# 7_-RGMII_SDIO_SPI_GPIOs_etc.net
KiCad netlist of a schematic drawn in Altium Designer
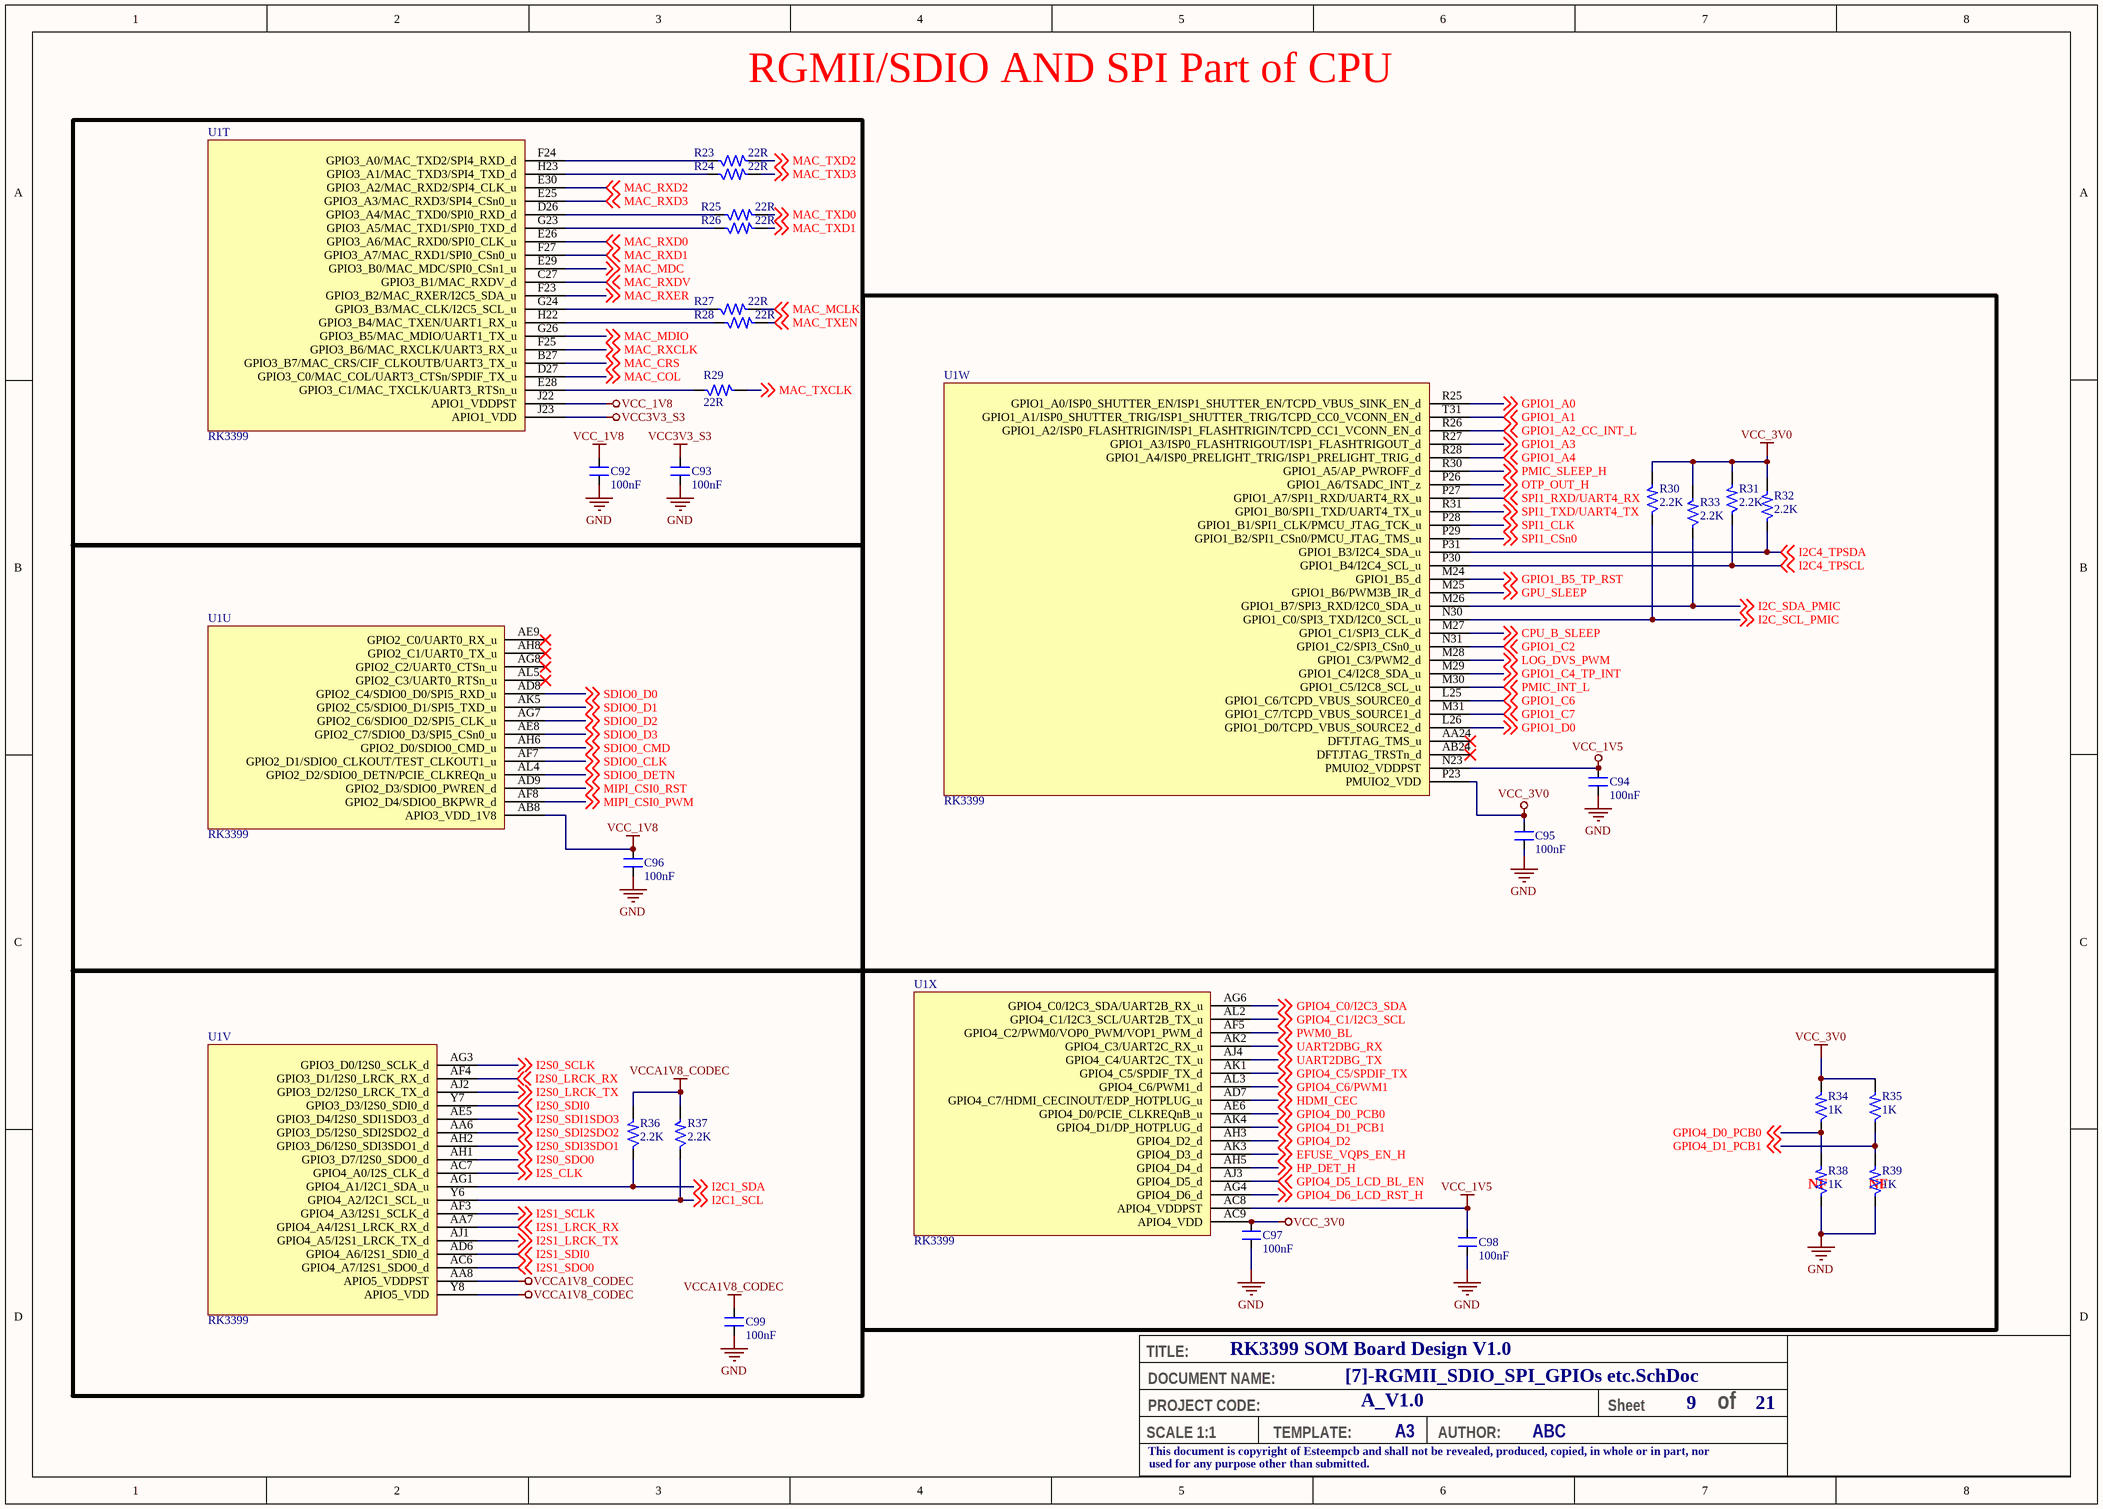
[diagram p0: [7]-RGMII_SDIO_SPI_GPIOs etc.SchDoc]

(export (version "E")
  (design (tool "Eeschema 10.0.6"))
  (components
    (comp (ref "C92")
      (value "100nF")
      (footprint "CAP_0201")
      (description "0.1µF ±10% 25V Ceramic Capacitor X5R 0201 (0603 Metric)")
      (fields
        (field (name "MANUFACTURER") "TDK Corporation")
        (field (name "MANUFACTURER PART NUMBER") "C0603X5R1E104K030BB")
      )
      (libsource (lib "RK3399 _Module_Intlib") (part "CAP_100nF-25V-10%-0201"))
    )
    (comp (ref "C93")
      (value "100nF")
      (footprint "CAP_0201")
      (description "0.1µF ±10% 25V Ceramic Capacitor X5R 0201 (0603 Metric)")
      (fields
        (field (name "MANUFACTURER") "TDK Corporation")
        (field (name "MANUFACTURER PART NUMBER") "C0603X5R1E104K030BB")
      )
      (libsource (lib "RK3399 _Module_Intlib") (part "CAP_100nF-25V-10%-0201"))
    )
    (comp (ref "C94")
      (value "100nF")
      (footprint "CAP_0201")
      (description "0.1µF ±10% 25V Ceramic Capacitor X5R 0201 (0603 Metric)")
      (fields
        (field (name "MANUFACTURER") "TDK Corporation")
        (field (name "MANUFACTURER PART NUMBER") "C0603X5R1E104K030BB")
      )
      (libsource (lib "RK3399 _Module_Intlib") (part "CAP_100nF-25V-10%-0201"))
    )
    (comp (ref "C95")
      (value "100nF")
      (footprint "CAP_0201")
      (description "0.1µF ±10% 25V Ceramic Capacitor X5R 0201 (0603 Metric)")
      (fields
        (field (name "MANUFACTURER") "TDK Corporation")
        (field (name "MANUFACTURER PART NUMBER") "C0603X5R1E104K030BB")
      )
      (libsource (lib "RK3399 _Module_Intlib") (part "CAP_100nF-25V-10%-0201"))
    )
    (comp (ref "C96")
      (value "100nF")
      (footprint "CAP_0201")
      (description "0.1µF ±10% 25V Ceramic Capacitor X5R 0201 (0603 Metric)")
      (fields
        (field (name "MANUFACTURER") "TDK Corporation")
        (field (name "MANUFACTURER PART NUMBER") "C0603X5R1E104K030BB")
      )
      (libsource (lib "RK3399 _Module_Intlib") (part "CAP_100nF-25V-10%-0201"))
    )
    (comp (ref "C97")
      (value "100nF")
      (footprint "CAP_0201")
      (description "0.1µF ±10% 25V Ceramic Capacitor X5R 0201 (0603 Metric)")
      (fields
        (field (name "MANUFACTURER") "TDK Corporation")
        (field (name "MANUFACTURER PART NUMBER") "C0603X5R1E104K030BB")
      )
      (libsource (lib "RK3399 _Module_Intlib") (part "CAP_100nF-25V-10%-0201"))
    )
    (comp (ref "C98")
      (value "100nF")
      (footprint "CAP_0201")
      (description "0.1µF ±10% 25V Ceramic Capacitor X5R 0201 (0603 Metric)")
      (fields
        (field (name "MANUFACTURER") "TDK Corporation")
        (field (name "MANUFACTURER PART NUMBER") "C0603X5R1E104K030BB")
      )
      (libsource (lib "RK3399 _Module_Intlib") (part "CAP_100nF-25V-10%-0201"))
    )
    (comp (ref "C99")
      (value "100nF")
      (footprint "CAP_0201")
      (description "0.1µF ±10% 25V Ceramic Capacitor X5R 0201 (0603 Metric)")
      (fields
        (field (name "MANUFACTURER") "TDK Corporation")
        (field (name "MANUFACTURER PART NUMBER") "C0603X5R1E104K030BB")
      )
      (libsource (lib "RK3399 _Module_Intlib") (part "CAP_100nF-25V-10%-0201"))
    )
    (comp (ref "R23")
      (value "22R")
      (footprint "RES_0201")
      (description "22 Ohms ±1% 0.05W, 1/20W Chip Resistor 0201 (0603 Metric) Moisture Resistant Thick Film")
      (fields
        (field (name "MANUFACTURER") "Yageo")
        (field (name "MANUFACTURER PART NUMBER") "RC0201FR-0722RL")
      )
      (libsource (lib "EsteemPCB_SOM_Course_intlib") (part "RES_22R-0.05W-1%-0201"))
    )
    (comp (ref "R24")
      (value "22R")
      (footprint "RES_0201")
      (description "22 Ohms ±1% 0.05W, 1/20W Chip Resistor 0201 (0603 Metric) Moisture Resistant Thick Film")
      (fields
        (field (name "MANUFACTURER") "Yageo")
        (field (name "MANUFACTURER PART NUMBER") "RC0201FR-0722RL")
      )
      (libsource (lib "EsteemPCB_SOM_Course_intlib") (part "RES_22R-0.05W-1%-0201"))
    )
    (comp (ref "R25")
      (value "22R")
      (footprint "RES_0201")
      (description "22 Ohms ±1% 0.05W, 1/20W Chip Resistor 0201 (0603 Metric) Moisture Resistant Thick Film")
      (fields
        (field (name "MANUFACTURER") "Yageo")
        (field (name "MANUFACTURER PART NUMBER") "RC0201FR-0722RL")
      )
      (libsource (lib "EsteemPCB_SOM_Course_intlib") (part "RES_22R-0.05W-1%-0201"))
    )
    (comp (ref "R26")
      (value "22R")
      (footprint "RES_0201")
      (description "22 Ohms ±1% 0.05W, 1/20W Chip Resistor 0201 (0603 Metric) Moisture Resistant Thick Film")
      (fields
        (field (name "MANUFACTURER") "Yageo")
        (field (name "MANUFACTURER PART NUMBER") "RC0201FR-0722RL")
      )
      (libsource (lib "EsteemPCB_SOM_Course_intlib") (part "RES_22R-0.05W-1%-0201"))
    )
    (comp (ref "R27")
      (value "22R")
      (footprint "RES_0201")
      (description "22 Ohms ±1% 0.05W, 1/20W Chip Resistor 0201 (0603 Metric) Moisture Resistant Thick Film")
      (fields
        (field (name "MANUFACTURER") "Yageo")
        (field (name "MANUFACTURER PART NUMBER") "RC0201FR-0722RL")
      )
      (libsource (lib "EsteemPCB_SOM_Course_intlib") (part "RES_22R-0.05W-1%-0201"))
    )
    (comp (ref "R28")
      (value "22R")
      (footprint "RES_0201")
      (description "22 Ohms ±1% 0.05W, 1/20W Chip Resistor 0201 (0603 Metric) Moisture Resistant Thick Film")
      (fields
        (field (name "MANUFACTURER") "Yageo")
        (field (name "MANUFACTURER PART NUMBER") "RC0201FR-0722RL")
      )
      (libsource (lib "EsteemPCB_SOM_Course_intlib") (part "RES_22R-0.05W-1%-0201"))
    )
    (comp (ref "R29")
      (value "22R")
      (footprint "RES_0201")
      (description "22 Ohms ±1% 0.05W, 1/20W Chip Resistor 0201 (0603 Metric) Moisture Resistant Thick Film")
      (fields
        (field (name "MANUFACTURER") "Yageo")
        (field (name "MANUFACTURER PART NUMBER") "RC0201FR-0722RL")
      )
      (libsource (lib "EsteemPCB_SOM_Course_intlib") (part "RES_22R-0.05W-1%-0201"))
    )
    (comp (ref "R30")
      (value "2.2K")
      (footprint "RES_0201")
      (description "2.2 kOhms ±1% 0.05W, 1/20W Chip Resistor 0201 (0603 Metric) Thick Film")
      (fields
        (field (name "MANUFACTURER") "Stackpole Electronics Inc")
        (field (name "MANUFACTURER PART NUMBER") "RMCF0201FT2K20")
      )
      (libsource (lib "RK3399 _Module_Intlib") (part "RES_2.2K-0.05W-1%-0201"))
    )
    (comp (ref "R31")
      (value "2.2K")
      (footprint "RES_0201")
      (description "2.2 kOhms ±1% 0.05W, 1/20W Chip Resistor 0201 (0603 Metric) Thick Film")
      (fields
        (field (name "MANUFACTURER") "Stackpole Electronics Inc")
        (field (name "MANUFACTURER PART NUMBER") "RMCF0201FT2K20")
      )
      (libsource (lib "RK3399 _Module_Intlib") (part "RES_2.2K-0.05W-1%-0201"))
    )
    (comp (ref "R32")
      (value "2.2K")
      (footprint "RES_0201")
      (description "2.2 kOhms ±1% 0.05W, 1/20W Chip Resistor 0201 (0603 Metric) Thick Film")
      (fields
        (field (name "MANUFACTURER") "Stackpole Electronics Inc")
        (field (name "MANUFACTURER PART NUMBER") "RMCF0201FT2K20")
      )
      (libsource (lib "RK3399 _Module_Intlib") (part "RES_2.2K-0.05W-1%-0201"))
    )
    (comp (ref "R33")
      (value "2.2K")
      (footprint "RES_0201")
      (description "2.2 kOhms ±1% 0.05W, 1/20W Chip Resistor 0201 (0603 Metric) Thick Film")
      (fields
        (field (name "MANUFACTURER") "Stackpole Electronics Inc")
        (field (name "MANUFACTURER PART NUMBER") "RMCF0201FT2K20")
      )
      (libsource (lib "RK3399 _Module_Intlib") (part "RES_2.2K-0.05W-1%-0201"))
    )
    (comp (ref "R34")
      (value "1K")
      (footprint "RES_0201")
      (description "1 kOhms ±1% 0.05W, 1/20W Chip Resistor 0201 (0603 Metric) Thick Film")
      (fields
        (field (name "MANUFACTURER") "Yageo")
        (field (name "MANUFACTURER PART NUMBER") "RC0201FR-071KL")
      )
      (libsource (lib "RK3399 _Module_Intlib") (part "RES_1K-0.05W-1%-0201"))
    )
    (comp (ref "R35")
      (value "1K")
      (footprint "RES_0201")
      (description "1 kOhms ±1% 0.05W, 1/20W Chip Resistor 0201 (0603 Metric) Thick Film")
      (fields
        (field (name "MANUFACTURER") "Yageo")
        (field (name "MANUFACTURER PART NUMBER") "RC0201FR-071KL")
      )
      (libsource (lib "RK3399 _Module_Intlib") (part "RES_1K-0.05W-1%-0201"))
    )
    (comp (ref "R36")
      (value "2.2K")
      (footprint "RES_0201")
      (description "2.2 kOhms ±1% 0.05W, 1/20W Chip Resistor 0201 (0603 Metric) Thick Film")
      (fields
        (field (name "MANUFACTURER") "Stackpole Electronics Inc")
        (field (name "MANUFACTURER PART NUMBER") "RMCF0201FT2K20")
      )
      (libsource (lib "RK3399 _Module_Intlib") (part "RES_2.2K-0.05W-1%-0201"))
    )
    (comp (ref "R37")
      (value "2.2K")
      (footprint "RES_0201")
      (description "2.2 kOhms ±1% 0.05W, 1/20W Chip Resistor 0201 (0603 Metric) Thick Film")
      (fields
        (field (name "MANUFACTURER") "Stackpole Electronics Inc")
        (field (name "MANUFACTURER PART NUMBER") "RMCF0201FT2K20")
      )
      (libsource (lib "RK3399 _Module_Intlib") (part "RES_2.2K-0.05W-1%-0201"))
    )
    (comp (ref "R38")
      (value "1K")
      (footprint "RES_0201")
      (description "1 kOhms ±1% 0.05W, 1/20W Chip Resistor 0201 (0603 Metric) Thick Film")
      (fields
        (field (name "MANUFACTURER") "Yageo")
        (field (name "MANUFACTURER PART NUMBER") "RC0201FR-071KL")
      )
      (libsource (lib "RK3399 _Module_Intlib") (part "RES_1K-0.05W-1%-0201"))
    )
    (comp (ref "R39")
      (value "1K")
      (footprint "RES_0201")
      (description "1 kOhms ±1% 0.05W, 1/20W Chip Resistor 0201 (0603 Metric) Thick Film")
      (fields
        (field (name "MANUFACTURER") "Yageo")
        (field (name "MANUFACTURER PART NUMBER") "RC0201FR-071KL")
      )
      (libsource (lib "RK3399 _Module_Intlib") (part "RES_1K-0.05W-1%-0201"))
    )
    (comp (ref "U1")
      (value "RK3399")
      (footprint "FBGA828_23_826X826")
      (description "RK3399 is a low power, high performance processor for computing, personal mobile.")
      (fields (field (name "MANUFACTURER") "Rockchip"))
      (libsource (lib "RK3399 _Module_Schlib") (part "IC_RK3399-FCBGA828"))
    )
  )
  (nets
    (net (code "1") (name "CPU_B_SLEEP") (class "Default")
      (node (ref "U1") (pin "M27") (pinfunction "GPIO1_C1/SPI3_CLK_d_M27") (pintype "passive"))
    )
    (net (code "2") (name "EFUSE_VQPS_EN_H") (class "Default")
      (node (ref "U1") (pin "AK3") (pinfunction "GPIO4_D3_d_AK3") (pintype "passive"))
    )
    (net (code "3") (name "GND") (class "Default")
      (node (ref "C92") (pin "1") (pinfunction "1_1") (pintype "passive"))
      (node (ref "C93") (pin "1") (pinfunction "1_1") (pintype "passive"))
      (node (ref "C94") (pin "1") (pinfunction "1_1") (pintype "passive"))
      (node (ref "C95") (pin "1") (pinfunction "1_1") (pintype "passive"))
      (node (ref "C96") (pin "1") (pinfunction "1_1") (pintype "passive"))
      (node (ref "C97") (pin "1") (pinfunction "1_1") (pintype "passive"))
      (node (ref "C98") (pin "1") (pinfunction "1_1") (pintype "passive"))
      (node (ref "C99") (pin "1") (pinfunction "1_1") (pintype "passive"))
      (node (ref "R38") (pin "1") (pinfunction "1_1") (pintype "passive"))
      (node (ref "R39") (pin "1") (pinfunction "1_1") (pintype "passive"))
    )
    (net (code "4") (name "GPIO1_A0") (class "Default")
      (node (ref "U1") (pin "R25") (pinfunction "GPIO1_A0/ISP0_SHUTTER_EN/ISP1_SHUTTER_EN/TCPD_VBUS_SINK_EN_d_R25") (pintype "passive"))
    )
    (net (code "5") (name "GPIO1_A1") (class "Default")
      (node (ref "U1") (pin "T31") (pinfunction "GPIO1_A1/ISP0_SHUTTER_TRIG/ISP1_SHUTTER_TRIG/TCPD_CC0_VCONN_EN_d_T31") (pintype "passive"))
    )
    (net (code "6") (name "GPIO1_A2_CC_INT_L") (class "Default")
      (node (ref "U1") (pin "R26") (pinfunction "GPIO1_A2/ISP0_FLASHTRIGIN/ISP1_FLASHTRIGIN/TCPD_CC1_VCONN_EN_d_R26") (pintype "passive"))
    )
    (net (code "7") (name "GPIO1_A3") (class "Default")
      (node (ref "U1") (pin "R27") (pinfunction "GPIO1_A3/ISP0_FLASHTRIGOUT/ISP1_FLASHTRIGOUT_d_R27") (pintype "passive"))
    )
    (net (code "8") (name "GPIO1_A4") (class "Default")
      (node (ref "U1") (pin "R28") (pinfunction "GPIO1_A4/ISP0_PRELIGHT_TRIG/ISP1_PRELIGHT_TRIG_d_R28") (pintype "passive"))
    )
    (net (code "9") (name "GPIO1_B5_TP_RST") (class "Default")
      (node (ref "U1") (pin "M24") (pinfunction "GPIO1_B5_d_M24") (pintype "passive"))
    )
    (net (code "10") (name "GPIO1_C2") (class "Default")
      (node (ref "U1") (pin "N31") (pinfunction "GPIO1_C2/SPI3_CSn0_u_N31") (pintype "passive"))
    )
    (net (code "11") (name "GPIO1_C4_TP_INT") (class "Default")
      (node (ref "U1") (pin "M29") (pinfunction "GPIO1_C4/I2C8_SDA_u_M29") (pintype "passive"))
    )
    (net (code "12") (name "GPIO1_C6") (class "Default")
      (node (ref "U1") (pin "L25") (pinfunction "GPIO1_C6/TCPD_VBUS_SOURCE0_d_L25") (pintype "passive"))
    )
    (net (code "13") (name "GPIO1_C7") (class "Default")
      (node (ref "U1") (pin "M31") (pinfunction "GPIO1_C7/TCPD_VBUS_SOURCE1_d_M31") (pintype "passive"))
    )
    (net (code "14") (name "GPIO1_D0") (class "Default")
      (node (ref "U1") (pin "L26") (pinfunction "GPIO1_D0/TCPD_VBUS_SOURCE2_d_L26") (pintype "passive"))
    )
    (net (code "15") (name "GPIO4_C0{slash}I2C3_SDA") (class "Default")
      (node (ref "U1") (pin "AG6") (pinfunction "GPIO4_C0/I2C3_SDA/UART2B_RX_u_AG6") (pintype "passive"))
    )
    (net (code "16") (name "GPIO4_C1{slash}I2C3_SCL") (class "Default")
      (node (ref "U1") (pin "AL2") (pinfunction "GPIO4_C1/I2C3_SCL/UART2B_TX_u_AL2") (pintype "passive"))
    )
    (net (code "17") (name "GPIO4_C5{slash}SPDIF_TX") (class "Default")
      (node (ref "U1") (pin "AK1") (pinfunction "GPIO4_C5/SPDIF_TX_d_AK1") (pintype "passive"))
    )
    (net (code "18") (name "GPIO4_C6{slash}PWM1") (class "Default")
      (node (ref "U1") (pin "AL3") (pinfunction "GPIO4_C6/PWM1_d_AL3") (pintype "passive"))
    )
    (net (code "19") (name "GPIO4_D0_PCB0") (class "Default")
      (node (ref "R34") (pin "1") (pinfunction "1_1") (pintype "passive"))
      (node (ref "R38") (pin "2") (pinfunction "2_2") (pintype "passive"))
      (node (ref "U1") (pin "AE6") (pinfunction "GPIO4_D0/PCIE_CLKREQnB_u_AE6") (pintype "passive"))
    )
    (net (code "20") (name "GPIO4_D1_PCB1") (class "Default")
      (node (ref "R35") (pin "1") (pinfunction "1_1") (pintype "passive"))
      (node (ref "R39") (pin "2") (pinfunction "2_2") (pintype "passive"))
      (node (ref "U1") (pin "AK4") (pinfunction "GPIO4_D1/DP_HOTPLUG_d_AK4") (pintype "passive"))
    )
    (net (code "21") (name "GPIO4_D2") (class "Default")
      (node (ref "U1") (pin "AH3") (pinfunction "GPIO4_D2_d_AH3") (pintype "passive"))
    )
    (net (code "22") (name "GPIO4_D5_LCD_BL_EN") (class "Default")
      (node (ref "U1") (pin "AJ3") (pinfunction "GPIO4_D5_d_AJ3") (pintype "passive"))
    )
    (net (code "23") (name "GPIO4_D6_LCD_RST_H") (class "Default")
      (node (ref "U1") (pin "AG4") (pinfunction "GPIO4_D6_d_AG4") (pintype "passive"))
    )
    (net (code "24") (name "GPU_SLEEP") (class "Default")
      (node (ref "U1") (pin "M25") (pinfunction "GPIO1_B6/PWM3B_IR_d_M25") (pintype "passive"))
    )
    (net (code "25") (name "HDMI_CEC") (class "Default")
      (node (ref "U1") (pin "AD7") (pinfunction "GPIO4_C7/HDMI_CECINOUT/EDP_HOTPLUG_u_AD7") (pintype "passive"))
    )
    (net (code "26") (name "HP_DET_H") (class "Default")
      (node (ref "U1") (pin "AH5") (pinfunction "GPIO4_D4_d_AH5") (pintype "passive"))
    )
    (net (code "27") (name "I2C1_SCL") (class "Default")
      (node (ref "R37") (pin "1") (pinfunction "1_1") (pintype "passive"))
      (node (ref "U1") (pin "Y6") (pinfunction "GPIO4_A2/I2C1_SCL_u_Y6") (pintype "passive"))
    )
    (net (code "28") (name "I2C1_SDA") (class "Default")
      (node (ref "R36") (pin "1") (pinfunction "1_1") (pintype "passive"))
      (node (ref "U1") (pin "AG1") (pinfunction "GPIO4_A1/I2C1_SDA_u_AG1") (pintype "passive"))
    )
    (net (code "29") (name "I2C4_TPSCL") (class "Default")
      (node (ref "R31") (pin "1") (pinfunction "1_1") (pintype "passive"))
      (node (ref "U1") (pin "P30") (pinfunction "GPIO1_B4/I2C4_SCL_u_P30") (pintype "passive"))
    )
    (net (code "30") (name "I2C4_TPSDA") (class "Default")
      (node (ref "R32") (pin "1") (pinfunction "1_1") (pintype "passive"))
      (node (ref "U1") (pin "P31") (pinfunction "GPIO1_B3/I2C4_SDA_u_P31") (pintype "passive"))
    )
    (net (code "31") (name "I2C_SCL_PMIC") (class "Default")
      (node (ref "R30") (pin "1") (pinfunction "1_1") (pintype "passive"))
      (node (ref "U1") (pin "N30") (pinfunction "GPIO1_C0/SPI3_TXD/I2C0_SCL_u_N30") (pintype "passive"))
    )
    (net (code "32") (name "I2C_SDA_PMIC") (class "Default")
      (node (ref "R33") (pin "1") (pinfunction "1_1") (pintype "passive"))
      (node (ref "U1") (pin "M26") (pinfunction "GPIO1_B7/SPI3_RXD/I2C0_SDA_u_M26") (pintype "passive"))
    )
    (net (code "33") (name "I2S0_LRCK_RX") (class "Default")
      (node (ref "U1") (pin "AF4") (pinfunction "GPIO3_D1/I2S0_LRCK_RX_d_AF4") (pintype "passive"))
    )
    (net (code "34") (name "I2S0_LRCK_TX") (class "Default")
      (node (ref "U1") (pin "AJ2") (pinfunction "GPIO3_D2/I2S0_LRCK_TX_d_AJ2") (pintype "passive"))
    )
    (net (code "35") (name "I2S0_SCLK") (class "Default")
      (node (ref "U1") (pin "AG3") (pinfunction "GPIO3_D0/I2S0_SCLK_d_AG3") (pintype "passive"))
    )
    (net (code "36") (name "I2S0_SDI0") (class "Default")
      (node (ref "U1") (pin "Y7") (pinfunction "GPIO3_D3/I2S0_SDI0_d_Y7") (pintype "passive"))
    )
    (net (code "37") (name "I2S0_SDI1SDO3") (class "Default")
      (node (ref "U1") (pin "AE5") (pinfunction "GPIO3_D4/I2S0_SDI1SDO3_d_AE5") (pintype "passive"))
    )
    (net (code "38") (name "I2S0_SDI2SDO2") (class "Default")
      (node (ref "U1") (pin "AA6") (pinfunction "GPIO3_D5/I2S0_SDI2SDO2_d_AA6") (pintype "passive"))
    )
    (net (code "39") (name "I2S0_SDI3SDO1") (class "Default")
      (node (ref "U1") (pin "AH2") (pinfunction "GPIO3_D6/I2S0_SDI3SDO1_d_AH2") (pintype "passive"))
    )
    (net (code "40") (name "I2S0_SDO0") (class "Default")
      (node (ref "U1") (pin "AH1") (pinfunction "GPIO3_D7/I2S0_SDO0_d_AH1") (pintype "passive"))
    )
    (net (code "41") (name "I2S1_LRCK_RX") (class "Default")
      (node (ref "U1") (pin "AA7") (pinfunction "GPIO4_A4/I2S1_LRCK_RX_d_AA7") (pintype "passive"))
    )
    (net (code "42") (name "I2S1_LRCK_TX") (class "Default")
      (node (ref "U1") (pin "AJ1") (pinfunction "GPIO4_A5/I2S1_LRCK_TX_d_AJ1") (pintype "passive"))
    )
    (net (code "43") (name "I2S1_SCLK") (class "Default")
      (node (ref "U1") (pin "AF3") (pinfunction "GPIO4_A3/I2S1_SCLK_d_AF3") (pintype "passive"))
    )
    (net (code "44") (name "I2S1_SDI0") (class "Default")
      (node (ref "U1") (pin "AD6") (pinfunction "GPIO4_A6/I2S1_SDI0_d_AD6") (pintype "passive"))
    )
    (net (code "45") (name "I2S1_SDO0") (class "Default")
      (node (ref "U1") (pin "AC6") (pinfunction "GPIO4_A7/I2S1_SDO0_d_AC6") (pintype "passive"))
    )
    (net (code "46") (name "I2S_CLK") (class "Default")
      (node (ref "U1") (pin "AC7") (pinfunction "GPIO4_A0/I2S_CLK_d_AC7") (pintype "passive"))
    )
    (net (code "47") (name "LOG_DVS_PWM") (class "Default")
      (node (ref "U1") (pin "M28") (pinfunction "GPIO1_C3/PWM2_d_M28") (pintype "passive"))
    )
    (net (code "48") (name "MAC_COL") (class "Default")
      (node (ref "U1") (pin "D27") (pinfunction "GPIO3_C0/MAC_COL/UART3_CTSn/SPDIF_TX_u_D27") (pintype "passive"))
    )
    (net (code "49") (name "MAC_CRS") (class "Default")
      (node (ref "U1") (pin "B27") (pinfunction "GPIO3_B7/MAC_CRS/CIF_CLKOUTB/UART3_TX_u_B27") (pintype "passive"))
    )
    (net (code "50") (name "MAC_MCLK") (class "Default")
      (node (ref "R27") (pin "2") (pinfunction "2_2") (pintype "passive"))
    )
    (net (code "51") (name "MAC_MDC") (class "Default")
      (node (ref "U1") (pin "E29") (pinfunction "GPIO3_B0/MAC_MDC/SPI0_CSn1_u_E29") (pintype "passive"))
    )
    (net (code "52") (name "MAC_MDIO") (class "Default")
      (node (ref "U1") (pin "G26") (pinfunction "GPIO3_B5/MAC_MDIO/UART1_TX_u_G26") (pintype "passive"))
    )
    (net (code "53") (name "MAC_RXCLK") (class "Default")
      (node (ref "U1") (pin "F25") (pinfunction "GPIO3_B6/MAC_RXCLK/UART3_RX_u_F25") (pintype "passive"))
    )
    (net (code "54") (name "MAC_RXD0") (class "Default")
      (node (ref "U1") (pin "E26") (pinfunction "GPIO3_A6/MAC_RXD0/SPI0_CLK_u_E26") (pintype "passive"))
    )
    (net (code "55") (name "MAC_RXD1") (class "Default")
      (node (ref "U1") (pin "F27") (pinfunction "GPIO3_A7/MAC_RXD1/SPI0_CSn0_u_F27") (pintype "passive"))
    )
    (net (code "56") (name "MAC_RXD2") (class "Default")
      (node (ref "U1") (pin "E30") (pinfunction "GPIO3_A2/MAC_RXD2/SPI4_CLK_u_E30") (pintype "passive"))
    )
    (net (code "57") (name "MAC_RXD3") (class "Default")
      (node (ref "U1") (pin "E25") (pinfunction "GPIO3_A3/MAC_RXD3/SPI4_CSn0_u_E25") (pintype "passive"))
    )
    (net (code "58") (name "MAC_RXDV") (class "Default")
      (node (ref "U1") (pin "C27") (pinfunction "GPIO3_B1/MAC_RXDV_d_C27") (pintype "passive"))
    )
    (net (code "59") (name "MAC_RXER") (class "Default")
      (node (ref "U1") (pin "F23") (pinfunction "GPIO3_B2/MAC_RXER/I2C5_SDA_u_F23") (pintype "passive"))
    )
    (net (code "60") (name "MAC_TXCLK") (class "Default")
      (node (ref "R29") (pin "2") (pinfunction "2_2") (pintype "passive"))
    )
    (net (code "61") (name "MAC_TXD0") (class "Default")
      (node (ref "R25") (pin "2") (pinfunction "2_2") (pintype "passive"))
    )
    (net (code "62") (name "MAC_TXD1") (class "Default")
      (node (ref "R26") (pin "2") (pinfunction "2_2") (pintype "passive"))
    )
    (net (code "63") (name "MAC_TXD2") (class "Default")
      (node (ref "R23") (pin "2") (pinfunction "2_2") (pintype "passive"))
    )
    (net (code "64") (name "MAC_TXD3") (class "Default")
      (node (ref "R24") (pin "2") (pinfunction "2_2") (pintype "passive"))
    )
    (net (code "65") (name "MAC_TXEN") (class "Default")
      (node (ref "R28") (pin "2") (pinfunction "2_2") (pintype "passive"))
    )
    (net (code "66") (name "MIPI_CSI0_PWM") (class "Default")
      (node (ref "U1") (pin "AF8") (pinfunction "GPIO2_D4/SDIO0_BKPWR_d_AF8") (pintype "passive"))
    )
    (net (code "67") (name "MIPI_CSI0_RST") (class "Default")
      (node (ref "U1") (pin "AD9") (pinfunction "GPIO2_D3/SDIO0_PWREN_d_AD9") (pintype "passive"))
    )
    (net (code "68") (name "Net-(U1T-GPIO3_A0{slash}MAC_TXD2{slash}SPI4_RXD_d)") (class "Default")
      (node (ref "R23") (pin "1") (pinfunction "1_1") (pintype "passive"))
      (node (ref "U1") (pin "F24") (pinfunction "GPIO3_A0/MAC_TXD2/SPI4_RXD_d_F24") (pintype "passive"))
    )
    (net (code "69") (name "Net-(U1T-GPIO3_A1{slash}MAC_TXD3{slash}SPI4_TXD_d)") (class "Default")
      (node (ref "R24") (pin "1") (pinfunction "1_1") (pintype "passive"))
      (node (ref "U1") (pin "H23") (pinfunction "GPIO3_A1/MAC_TXD3/SPI4_TXD_d_H23") (pintype "passive"))
    )
    (net (code "70") (name "Net-(U1T-GPIO3_A4{slash}MAC_TXD0{slash}SPI0_RXD_d)") (class "Default")
      (node (ref "R25") (pin "1") (pinfunction "1_1") (pintype "passive"))
      (node (ref "U1") (pin "D26") (pinfunction "GPIO3_A4/MAC_TXD0/SPI0_RXD_d_D26") (pintype "passive"))
    )
    (net (code "71") (name "Net-(U1T-GPIO3_A5{slash}MAC_TXD1{slash}SPI0_TXD_d)") (class "Default")
      (node (ref "R26") (pin "1") (pinfunction "1_1") (pintype "passive"))
      (node (ref "U1") (pin "G23") (pinfunction "GPIO3_A5/MAC_TXD1/SPI0_TXD_d_G23") (pintype "passive"))
    )
    (net (code "72") (name "Net-(U1T-GPIO3_B3{slash}MAC_CLK{slash}I2C5_SCL_u)") (class "Default")
      (node (ref "R27") (pin "1") (pinfunction "1_1") (pintype "passive"))
      (node (ref "U1") (pin "G24") (pinfunction "GPIO3_B3/MAC_CLK/I2C5_SCL_u_G24") (pintype "passive"))
    )
    (net (code "73") (name "Net-(U1T-GPIO3_B4{slash}MAC_TXEN{slash}UART1_RX_u)") (class "Default")
      (node (ref "R28") (pin "1") (pinfunction "1_1") (pintype "passive"))
      (node (ref "U1") (pin "H22") (pinfunction "GPIO3_B4/MAC_TXEN/UART1_RX_u_H22") (pintype "passive"))
    )
    (net (code "74") (name "Net-(U1T-GPIO3_C1{slash}MAC_TXCLK{slash}UART3_RTSn_u)") (class "Default")
      (node (ref "R29") (pin "1") (pinfunction "1_1") (pintype "passive"))
      (node (ref "U1") (pin "E28") (pinfunction "GPIO3_C1/MAC_TXCLK/UART3_RTSn_u_E28") (pintype "passive"))
    )
    (net (code "75") (name "OTP_OUT_H") (class "Default")
      (node (ref "U1") (pin "P26") (pinfunction "GPIO1_A6/TSADC_INT_z_P26") (pintype "passive"))
    )
    (net (code "76") (name "PMIC_INT_L") (class "Default")
      (node (ref "U1") (pin "M30") (pinfunction "GPIO1_C5/I2C8_SCL_u_M30") (pintype "passive"))
    )
    (net (code "77") (name "PMIC_SLEEP_H") (class "Default")
      (node (ref "U1") (pin "R30") (pinfunction "GPIO1_A5/AP_PWROFF_d_R30") (pintype "passive"))
    )
    (net (code "78") (name "PWM0_BL") (class "Default")
      (node (ref "U1") (pin "AF5") (pinfunction "GPIO4_C2/PWM0/VOP0_PWM/VOP1_PWM_d_AF5") (pintype "passive"))
    )
    (net (code "79") (name "SDIO0_CLK") (class "Default")
      (node (ref "U1") (pin "AF7") (pinfunction "GPIO2_D1/SDIO0_CLKOUT/TEST_CLKOUT1_u_AF7") (pintype "passive"))
    )
    (net (code "80") (name "SDIO0_CMD") (class "Default")
      (node (ref "U1") (pin "AH6") (pinfunction "GPIO2_D0/SDIO0_CMD_u_AH6") (pintype "passive"))
    )
    (net (code "81") (name "SDIO0_D0") (class "Default")
      (node (ref "U1") (pin "AD8") (pinfunction "GPIO2_C4/SDIO0_D0/SPI5_RXD_u_AD8") (pintype "passive"))
    )
    (net (code "82") (name "SDIO0_D1") (class "Default")
      (node (ref "U1") (pin "AK5") (pinfunction "GPIO2_C5/SDIO0_D1/SPI5_TXD_u_AK5") (pintype "passive"))
    )
    (net (code "83") (name "SDIO0_D2") (class "Default")
      (node (ref "U1") (pin "AG7") (pinfunction "GPIO2_C6/SDIO0_D2/SPI5_CLK_u_AG7") (pintype "passive"))
    )
    (net (code "84") (name "SDIO0_D3") (class "Default")
      (node (ref "U1") (pin "AE8") (pinfunction "GPIO2_C7/SDIO0_D3/SPI5_CSn0_u_AE8") (pintype "passive"))
    )
    (net (code "85") (name "SDIO0_DETN") (class "Default")
      (node (ref "U1") (pin "AL4") (pinfunction "GPIO2_D2/SDIO0_DETN/PCIE_CLKREQn_u_AL4") (pintype "passive"))
    )
    (net (code "86") (name "SPI1_CLK") (class "Default")
      (node (ref "U1") (pin "P28") (pinfunction "GPIO1_B1/SPI1_CLK/PMCU_JTAG_TCK_u_P28") (pintype "passive"))
    )
    (net (code "87") (name "SPI1_CSn0") (class "Default")
      (node (ref "U1") (pin "P29") (pinfunction "GPIO1_B2/SPI1_CSn0/PMCU_JTAG_TMS_u_P29") (pintype "passive"))
    )
    (net (code "88") (name "SPI1_RXD{slash}UART4_RX") (class "Default")
      (node (ref "U1") (pin "P27") (pinfunction "GPIO1_A7/SPI1_RXD/UART4_RX_u_P27") (pintype "passive"))
    )
    (net (code "89") (name "SPI1_TXD{slash}UART4_TX") (class "Default")
      (node (ref "U1") (pin "R31") (pinfunction "GPIO1_B0/SPI1_TXD/UART4_TX_u_R31") (pintype "passive"))
    )
    (net (code "90") (name "UART2DBG_RX") (class "Default")
      (node (ref "U1") (pin "AK2") (pinfunction "GPIO4_C3/UART2C_RX_u_AK2") (pintype "passive"))
    )
    (net (code "91") (name "UART2DBG_TX") (class "Default")
      (node (ref "U1") (pin "AJ4") (pinfunction "GPIO4_C4/UART2C_TX_u_AJ4") (pintype "passive"))
    )
    (net (code "92") (name "VCC3V3_S3") (class "Default")
      (node (ref "C93") (pin "2") (pinfunction "2_2") (pintype "passive"))
      (node (ref "U1") (pin "J23") (pinfunction "APIO1_VDD_J23") (pintype "passive"))
    )
    (net (code "93") (name "VCCA1V8_CODEC") (class "Default")
      (node (ref "C99") (pin "2") (pinfunction "2_2") (pintype "passive"))
      (node (ref "R36") (pin "2") (pinfunction "2_2") (pintype "passive"))
      (node (ref "R37") (pin "2") (pinfunction "2_2") (pintype "passive"))
      (node (ref "U1") (pin "AA8") (pinfunction "APIO5_VDDPST_AA8") (pintype "passive"))
      (node (ref "U1") (pin "Y8") (pinfunction "APIO5_VDD_Y8") (pintype "passive"))
    )
    (net (code "94") (name "VCC_1V5") (class "Default")
      (node (ref "C94") (pin "2") (pinfunction "2_2") (pintype "passive"))
      (node (ref "C98") (pin "2") (pinfunction "2_2") (pintype "passive"))
      (node (ref "U1") (pin "AC8") (pinfunction "APIO4_VDDPST_AC8") (pintype "passive"))
      (node (ref "U1") (pin "N23") (pinfunction "PMUIO2_VDDPST_N23") (pintype "passive"))
    )
    (net (code "95") (name "VCC_1V8") (class "Default")
      (node (ref "C92") (pin "2") (pinfunction "2_2") (pintype "passive"))
      (node (ref "C96") (pin "2") (pinfunction "2_2") (pintype "passive"))
      (node (ref "U1") (pin "AB8") (pinfunction "APIO3_VDD_1V8_AB8") (pintype "passive"))
      (node (ref "U1") (pin "J22") (pinfunction "APIO1_VDDPST_J22") (pintype "passive"))
    )
    (net (code "96") (name "VCC_3V0") (class "Default")
      (node (ref "C95") (pin "2") (pinfunction "2_2") (pintype "passive"))
      (node (ref "C97") (pin "2") (pinfunction "2_2") (pintype "passive"))
      (node (ref "R30") (pin "2") (pinfunction "2_2") (pintype "passive"))
      (node (ref "R31") (pin "2") (pinfunction "2_2") (pintype "passive"))
      (node (ref "R32") (pin "2") (pinfunction "2_2") (pintype "passive"))
      (node (ref "R33") (pin "2") (pinfunction "2_2") (pintype "passive"))
      (node (ref "R34") (pin "2") (pinfunction "2_2") (pintype "passive"))
      (node (ref "R35") (pin "2") (pinfunction "2_2") (pintype "passive"))
      (node (ref "U1") (pin "AC9") (pinfunction "APIO4_VDD_AC9") (pintype "passive"))
      (node (ref "U1") (pin "P23") (pinfunction "PMUIO2_VDD_P23") (pintype "passive"))
    )
    (net (code "97") (name "unconnected-(U1U-GPIO2_C0{slash}UART0_RX_u-PadAE9)") (class "Default")
      (node (ref "U1") (pin "AE9") (pinfunction "GPIO2_C0/UART0_RX_u_AE9") (pintype "passive+no_connect"))
    )
    (net (code "98") (name "unconnected-(U1U-GPIO2_C1{slash}UART0_TX_u-PadAH8)") (class "Default")
      (node (ref "U1") (pin "AH8") (pinfunction "GPIO2_C1/UART0_TX_u_AH8") (pintype "passive+no_connect"))
    )
    (net (code "99") (name "unconnected-(U1U-GPIO2_C2{slash}UART0_CTSn_u-PadAG8)") (class "Default")
      (node (ref "U1") (pin "AG8") (pinfunction "GPIO2_C2/UART0_CTSn_u_AG8") (pintype "passive+no_connect"))
    )
    (net (code "100") (name "unconnected-(U1U-GPIO2_C3{slash}UART0_RTSn_u-PadAL5)") (class "Default")
      (node (ref "U1") (pin "AL5") (pinfunction "GPIO2_C3/UART0_RTSn_u_AL5") (pintype "passive+no_connect"))
    )
    (net (code "101") (name "unconnected-(U1W-DFTJTAG_TMS_u-PadAA24)") (class "Default")
      (node (ref "U1") (pin "AA24") (pinfunction "DFTJTAG_TMS_u_AA24") (pintype "passive+no_connect"))
    )
    (net (code "102") (name "unconnected-(U1W-DFTJTAG_TRSTn_d-PadAB24)") (class "Default")
      (node (ref "U1") (pin "AB24") (pinfunction "DFTJTAG_TRSTn_d_AB24") (pintype "passive+no_connect"))
    )
  )
)
